# windvane_v2.net
KiCad netlist of a schematic drawn in EAGLE
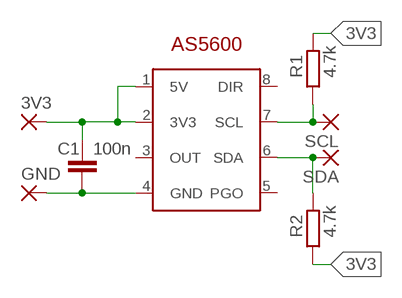
[diagram p0: schematic, sheet 1]

(export (version "E")
  (design (tool "Eeschema 10.0.6"))
  (components
    (comp (ref "3V3")
      (value "1,6/0,8")
      (footprint "eagle-import:1,6_0,8")
      (libsource (lib "eagle-import") (part "1,6/0,8"))
    )
    (comp (ref "C1")
      (value "100n")
      (footprint "eagle-import:C1206")
      (libsource (lib "eagle-import") (part "C-EUC1206"))
    )
    (comp (ref "GND")
      (value "1,6/0,8")
      (footprint "eagle-import:1,6_0,8")
      (libsource (lib "eagle-import") (part "1,6/0,8"))
    )
    (comp (ref "R1")
      (value "4.7k")
      (footprint "eagle-import:R1206")
      (libsource (lib "eagle-import") (part "R-EU_R1206"))
    )
    (comp (ref "R2")
      (value "4.7k")
      (footprint "eagle-import:R1206")
      (libsource (lib "eagle-import") (part "R-EU_R1206"))
    )
    (comp (ref "SCL")
      (value "1,6/0,8")
      (footprint "eagle-import:1,6_0,8")
      (libsource (lib "eagle-import") (part "1,6/0,8"))
    )
    (comp (ref "SDA")
      (value "1,6/0,8")
      (footprint "eagle-import:1,6_0,8")
      (libsource (lib "eagle-import") (part "1,6/0,8"))
    )
    (comp (ref "U$1")
      (value "AS5600")
      (footprint "eagle-import:SOIC127P600X175-8N")
      (libsource (lib "eagle-import") (part "AS5600"))
    )
  )
  (nets
    (net (code "1") (name "3V3") (class "Default")
      (node (ref "3V3") (pin "1") (pinfunction "P_1") (pintype "passive"))
      (node (ref "C1") (pin "1") (pinfunction "1_1") (pintype "passive"))
      (node (ref "R1") (pin "2") (pinfunction "2_2") (pintype "passive"))
      (node (ref "R2") (pin "1") (pinfunction "1_1") (pintype "passive"))
      (node (ref "U$1") (pin "1") (pinfunction "5V_1") (pintype "bidirectional"))
      (node (ref "U$1") (pin "2") (pinfunction "3V3_2") (pintype "bidirectional"))
    )
    (net (code "2") (name "Net-(GND-P)") (class "Default")
      (node (ref "C1") (pin "2") (pinfunction "2_2") (pintype "passive"))
      (node (ref "GND") (pin "1") (pinfunction "P_1") (pintype "passive"))
      (node (ref "U$1") (pin "4") (pinfunction "GND_4") (pintype "bidirectional"))
    )
    (net (code "3") (name "Net-(SCL-P)") (class "Default")
      (node (ref "R1") (pin "1") (pinfunction "1_1") (pintype "passive"))
      (node (ref "SCL") (pin "1") (pinfunction "P_1") (pintype "passive"))
      (node (ref "U$1") (pin "7") (pinfunction "SCL_7") (pintype "bidirectional"))
    )
    (net (code "4") (name "Net-(SDA-P)") (class "Default")
      (node (ref "R2") (pin "2") (pinfunction "2_2") (pintype "passive"))
      (node (ref "SDA") (pin "1") (pinfunction "P_1") (pintype "passive"))
      (node (ref "U$1") (pin "6") (pinfunction "SDA_6") (pintype "bidirectional"))
    )
    (net (code "5") (name "unconnected-(U$1-DIR-Pad8)") (class "Default")
      (node (ref "U$1") (pin "8") (pinfunction "DIR_8") (pintype "bidirectional"))
    )
    (net (code "6") (name "unconnected-(U$1-OUT-Pad3)") (class "Default")
      (node (ref "U$1") (pin "3") (pinfunction "OUT_3") (pintype "bidirectional"))
    )
    (net (code "7") (name "unconnected-(U$1-PGO-Pad5)") (class "Default")
      (node (ref "U$1") (pin "5") (pinfunction "PGO_5") (pintype "bidirectional"))
    )
  )
)
